# latch3.net
KiCad netlist of a schematic drawn in EAGLE
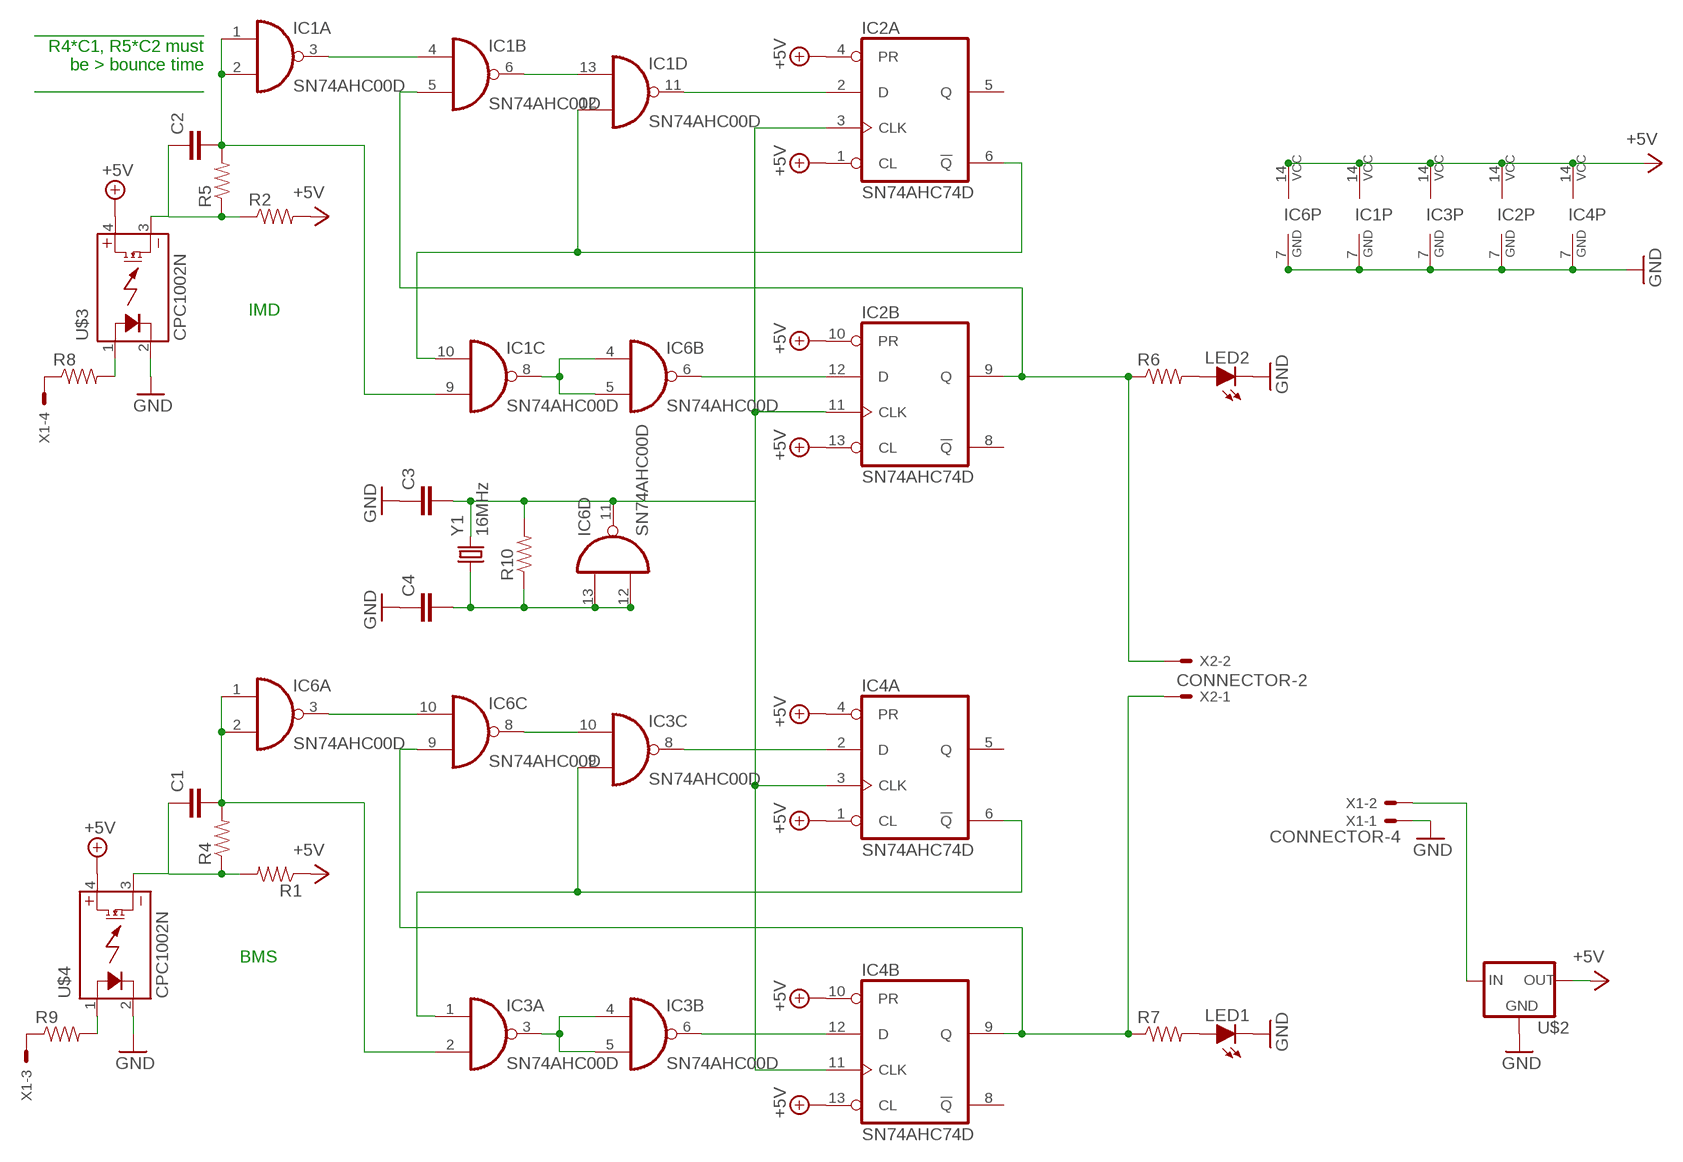
[diagram p0: schematic, sheet 1]

(export (version "E")
  (design (tool "Eeschema 10.0.6"))
  (components
    (comp (ref "C1")
      (value "CAP0402-CAP")
      (footprint "eagle-import:0402-CAP")
      (libsource (lib "eagle-import") (part "CAP0402-CAP"))
    )
    (comp (ref "C2")
      (value "CAP0402-CAP")
      (footprint "eagle-import:0402-CAP")
      (libsource (lib "eagle-import") (part "CAP0402-CAP"))
    )
    (comp (ref "C3")
      (value "CAP0402-CAP")
      (footprint "eagle-import:0402-CAP")
      (libsource (lib "eagle-import") (part "CAP0402-CAP"))
    )
    (comp (ref "C4")
      (value "CAP0402-CAP")
      (footprint "eagle-import:0402-CAP")
      (libsource (lib "eagle-import") (part "CAP0402-CAP"))
    )
    (comp (ref "IC1")
      (value "SN74AHC00D")
      (footprint "eagle-import:SOIC-14")
      (libsource (lib "eagle-import") (part "SN74AHC00D"))
    )
    (comp (ref "IC2")
      (value "SN74AHC74D")
      (footprint "eagle-import:SOIC-14")
      (libsource (lib "eagle-import") (part "SN74AHC74D"))
    )
    (comp (ref "IC3")
      (value "SN74AHC00D")
      (footprint "eagle-import:SOIC-14")
      (libsource (lib "eagle-import") (part "SN74AHC00D"))
    )
    (comp (ref "IC4")
      (value "SN74AHC74D")
      (footprint "eagle-import:SOIC-14")
      (libsource (lib "eagle-import") (part "SN74AHC74D"))
    )
    (comp (ref "IC6")
      (value "SN74AHC00D")
      (footprint "eagle-import:SOIC-14")
      (libsource (lib "eagle-import") (part "SN74AHC00D"))
    )
    (comp (ref "LED1")
      (value "LED-0805")
      (footprint "eagle-import:LED-805")
      (libsource (lib "eagle-import") (part "LED-0805"))
    )
    (comp (ref "LED2")
      (value "LED-0805")
      (footprint "eagle-import:LED-805")
      (libsource (lib "eagle-import") (part "LED-0805"))
    )
    (comp (ref "R1")
      (value "RESISTOR0402")
      (footprint "eagle-import:0402-RES")
      (libsource (lib "eagle-import") (part "RESISTOR0402"))
    )
    (comp (ref "R2")
      (value "RESISTOR0402")
      (footprint "eagle-import:0402-RES")
      (libsource (lib "eagle-import") (part "RESISTOR0402"))
    )
    (comp (ref "R4")
      (value "RESISTOR0402")
      (footprint "eagle-import:0402-RES")
      (libsource (lib "eagle-import") (part "RESISTOR0402"))
    )
    (comp (ref "R5")
      (value "RESISTOR0402")
      (footprint "eagle-import:0402-RES")
      (libsource (lib "eagle-import") (part "RESISTOR0402"))
    )
    (comp (ref "R6")
      (value "RESISTOR0402")
      (footprint "eagle-import:0402-RES")
      (libsource (lib "eagle-import") (part "RESISTOR0402"))
    )
    (comp (ref "R7")
      (value "RESISTOR0402")
      (footprint "eagle-import:0402-RES")
      (libsource (lib "eagle-import") (part "RESISTOR0402"))
    )
    (comp (ref "R8")
      (value "RESISTOR0402")
      (footprint "eagle-import:0402-RES")
      (libsource (lib "eagle-import") (part "RESISTOR0402"))
    )
    (comp (ref "R9")
      (value "RESISTOR0402")
      (footprint "eagle-import:0402-RES")
      (libsource (lib "eagle-import") (part "RESISTOR0402"))
    )
    (comp (ref "R10")
      (value "RESISTOR0402")
      (footprint "eagle-import:0402-RES")
      (libsource (lib "eagle-import") (part "RESISTOR0402"))
    )
    (comp (ref "U$2")
      (value "5VREG_LM340-NLM340MPX-5.0/NOPB")
      (footprint "eagle-import:SOT223")
      (libsource (lib "eagle-import") (part "5VREG_LM340-NLM340MPX-5.0/NOPB"))
    )
    (comp (ref "U$3")
      (value "CPC1002N")
      (footprint "eagle-import:SOP04")
      (libsource (lib "eagle-import") (part "CPC1002N"))
    )
    (comp (ref "U$4")
      (value "CPC1002N")
      (footprint "eagle-import:SOP04")
      (libsource (lib "eagle-import") (part "CPC1002N"))
    )
    (comp (ref "X1")
      (value "CONNECTOR-4")
      (footprint "eagle-import:MINIFIT_5566-4")
      (libsource (lib "eagle-import") (part "CONNECTOR-4"))
    )
    (comp (ref "X2")
      (value "CONNECTOR-2")
      (footprint "eagle-import:MINIFIT_5566-2")
      (libsource (lib "eagle-import") (part "CONNECTOR-2"))
    )
    (comp (ref "Y1")
      (value "16MHz")
      (footprint "eagle-import:CRYSTAL-SMD-3.2X1.5MM")
      (libsource (lib "eagle-import") (part "CRYSTAL3.2X1.5MM"))
    )
  )
  (nets
    (net (code "1") (name "+5V") (class "Default")
      (node (ref "IC1") (pin "14") (pinfunction "VCC_14") (pintype "power_in"))
      (node (ref "IC2") (pin "1") (pinfunction "CL_1") (pintype "input"))
      (node (ref "IC2") (pin "10") (pinfunction "PR_10") (pintype "input"))
      (node (ref "IC2") (pin "13") (pinfunction "CL_13") (pintype "input"))
      (node (ref "IC2") (pin "14") (pinfunction "VCC_14") (pintype "power_in"))
      (node (ref "IC2") (pin "4") (pinfunction "PR_4") (pintype "input"))
      (node (ref "IC3") (pin "14") (pinfunction "VCC_14") (pintype "power_in"))
      (node (ref "IC4") (pin "1") (pinfunction "CL_1") (pintype "input"))
      (node (ref "IC4") (pin "10") (pinfunction "PR_10") (pintype "input"))
      (node (ref "IC4") (pin "13") (pinfunction "CL_13") (pintype "input"))
      (node (ref "IC4") (pin "14") (pinfunction "VCC_14") (pintype "power_in"))
      (node (ref "IC4") (pin "4") (pinfunction "PR_4") (pintype "input"))
      (node (ref "IC6") (pin "14") (pinfunction "VCC_14") (pintype "power_in"))
      (node (ref "R1") (pin "1") (pinfunction "1_1") (pintype "passive"))
      (node (ref "R2") (pin "2") (pinfunction "2_2") (pintype "passive"))
      (node (ref "U$2") (pin "3") (pinfunction "OUT_3") (pintype "output"))
      (node (ref "U$3") (pin "4") (pinfunction "DC+_4") (pintype "passive"))
      (node (ref "U$4") (pin "4") (pinfunction "DC+_4") (pintype "passive"))
    )
    (net (code "2") (name "GND") (class "Default")
      (node (ref "C3") (pin "1") (pinfunction "1_1") (pintype "passive"))
      (node (ref "C4") (pin "1") (pinfunction "1_1") (pintype "passive"))
      (node (ref "IC1") (pin "7") (pinfunction "GND_7") (pintype "power_in"))
      (node (ref "IC2") (pin "7") (pinfunction "GND_7") (pintype "power_in"))
      (node (ref "IC3") (pin "7") (pinfunction "GND_7") (pintype "power_in"))
      (node (ref "IC4") (pin "7") (pinfunction "GND_7") (pintype "power_in"))
      (node (ref "IC6") (pin "7") (pinfunction "GND_7") (pintype "power_in"))
      (node (ref "LED1") (pin "C") (pinfunction "C_C") (pintype "passive"))
      (node (ref "LED2") (pin "C") (pinfunction "C_C") (pintype "passive"))
      (node (ref "U$2") (pin "2") (pinfunction "GND_2") (pintype "input"))
      (node (ref "U$2") (pin "4") (pinfunction "GND_4") (pintype "input"))
      (node (ref "U$3") (pin "2") (pinfunction "CONTROL-_2") (pintype "passive"))
      (node (ref "U$4") (pin "2") (pinfunction "CONTROL-_2") (pintype "passive"))
      (node (ref "X1") (pin "1") (pinfunction "S_1") (pintype "passive"))
    )
    (net (code "3") (name "Net-(IC1A-I0)") (class "Default")
      (node (ref "C2") (pin "2") (pinfunction "2_2") (pintype "passive"))
      (node (ref "IC1") (pin "1") (pinfunction "I0_1") (pintype "input"))
      (node (ref "IC1") (pin "2") (pinfunction "I1_2") (pintype "input"))
      (node (ref "IC1") (pin "9") (pinfunction "I1_9") (pintype "input"))
      (node (ref "R5") (pin "2") (pinfunction "2_2") (pintype "passive"))
    )
    (net (code "4") (name "Net-(IC1A-O)") (class "Default")
      (node (ref "IC1") (pin "3") (pinfunction "O_3") (pintype "output"))
      (node (ref "IC1") (pin "4") (pinfunction "I0_4") (pintype "input"))
    )
    (net (code "5") (name "Net-(IC1B-I1)") (class "Default")
      (node (ref "IC1") (pin "5") (pinfunction "I1_5") (pintype "input"))
      (node (ref "IC2") (pin "9") (pinfunction "Q_9") (pintype "output"))
      (node (ref "R6") (pin "1") (pinfunction "1_1") (pintype "passive"))
      (node (ref "X2") (pin "2") (pinfunction "S_2") (pintype "passive"))
    )
    (net (code "6") (name "Net-(IC1B-O)") (class "Default")
      (node (ref "IC1") (pin "13") (pinfunction "I0_13") (pintype "input"))
      (node (ref "IC1") (pin "6") (pinfunction "O_6") (pintype "output"))
    )
    (net (code "7") (name "Net-(IC1C-I0)") (class "Default")
      (node (ref "IC1") (pin "10") (pinfunction "I0_10") (pintype "input"))
      (node (ref "IC1") (pin "12") (pinfunction "I1_12") (pintype "input"))
      (node (ref "IC2") (pin "6") (pinfunction "~{Q}_6") (pintype "output"))
    )
    (net (code "8") (name "Net-(IC1C-O)") (class "Default")
      (node (ref "IC1") (pin "8") (pinfunction "O_8") (pintype "output"))
      (node (ref "IC6") (pin "4") (pinfunction "I0_4") (pintype "input"))
      (node (ref "IC6") (pin "5") (pinfunction "I1_5") (pintype "input"))
    )
    (net (code "9") (name "Net-(IC1D-O)") (class "Default")
      (node (ref "IC1") (pin "11") (pinfunction "O_11") (pintype "output"))
      (node (ref "IC2") (pin "2") (pinfunction "D_2") (pintype "input"))
    )
    (net (code "10") (name "Net-(IC2A-CLK)") (class "Default")
      (node (ref "C3") (pin "2") (pinfunction "2_2") (pintype "passive"))
      (node (ref "IC2") (pin "11") (pinfunction "CLK_11") (pintype "input"))
      (node (ref "IC2") (pin "3") (pinfunction "CLK_3") (pintype "input"))
      (node (ref "IC4") (pin "11") (pinfunction "CLK_11") (pintype "input"))
      (node (ref "IC4") (pin "3") (pinfunction "CLK_3") (pintype "input"))
      (node (ref "IC6") (pin "11") (pinfunction "O_11") (pintype "output"))
      (node (ref "R10") (pin "2") (pinfunction "2_2") (pintype "passive"))
      (node (ref "Y1") (pin "P$2") (pinfunction "2_P$2") (pintype "passive"))
    )
    (net (code "11") (name "Net-(IC2B-D)") (class "Default")
      (node (ref "IC2") (pin "12") (pinfunction "D_12") (pintype "input"))
      (node (ref "IC6") (pin "6") (pinfunction "O_6") (pintype "output"))
    )
    (net (code "12") (name "Net-(IC3A-I0)") (class "Default")
      (node (ref "IC3") (pin "1") (pinfunction "I0_1") (pintype "input"))
      (node (ref "IC3") (pin "9") (pinfunction "I1_9") (pintype "input"))
      (node (ref "IC4") (pin "6") (pinfunction "~{Q}_6") (pintype "output"))
    )
    (net (code "13") (name "Net-(IC3A-I1)") (class "Default")
      (node (ref "C1") (pin "2") (pinfunction "2_2") (pintype "passive"))
      (node (ref "IC3") (pin "2") (pinfunction "I1_2") (pintype "input"))
      (node (ref "IC6") (pin "1") (pinfunction "I0_1") (pintype "input"))
      (node (ref "IC6") (pin "2") (pinfunction "I1_2") (pintype "input"))
      (node (ref "R4") (pin "2") (pinfunction "2_2") (pintype "passive"))
    )
    (net (code "14") (name "Net-(IC3A-O)") (class "Default")
      (node (ref "IC3") (pin "3") (pinfunction "O_3") (pintype "output"))
      (node (ref "IC3") (pin "4") (pinfunction "I0_4") (pintype "input"))
      (node (ref "IC3") (pin "5") (pinfunction "I1_5") (pintype "input"))
    )
    (net (code "15") (name "Net-(IC3B-O)") (class "Default")
      (node (ref "IC3") (pin "6") (pinfunction "O_6") (pintype "output"))
      (node (ref "IC4") (pin "12") (pinfunction "D_12") (pintype "input"))
    )
    (net (code "16") (name "Net-(IC3C-I0)") (class "Default")
      (node (ref "IC3") (pin "10") (pinfunction "I0_10") (pintype "input"))
      (node (ref "IC6") (pin "8") (pinfunction "O_8") (pintype "output"))
    )
    (net (code "17") (name "Net-(IC3C-O)") (class "Default")
      (node (ref "IC3") (pin "8") (pinfunction "O_8") (pintype "output"))
      (node (ref "IC4") (pin "2") (pinfunction "D_2") (pintype "input"))
    )
    (net (code "18") (name "Net-(IC4B-Q)") (class "Default")
      (node (ref "IC4") (pin "9") (pinfunction "Q_9") (pintype "output"))
      (node (ref "IC6") (pin "9") (pinfunction "I1_9") (pintype "input"))
      (node (ref "R7") (pin "1") (pinfunction "1_1") (pintype "passive"))
      (node (ref "X2") (pin "1") (pinfunction "S_1") (pintype "passive"))
    )
    (net (code "19") (name "Net-(IC6A-O)") (class "Default")
      (node (ref "IC6") (pin "10") (pinfunction "I0_10") (pintype "input"))
      (node (ref "IC6") (pin "3") (pinfunction "O_3") (pintype "output"))
    )
    (net (code "20") (name "Net-(IC6D-I0)") (class "Default")
      (node (ref "C4") (pin "2") (pinfunction "2_2") (pintype "passive"))
      (node (ref "IC6") (pin "12") (pinfunction "I1_12") (pintype "input"))
      (node (ref "IC6") (pin "13") (pinfunction "I0_13") (pintype "input"))
      (node (ref "R10") (pin "1") (pinfunction "1_1") (pintype "passive"))
      (node (ref "Y1") (pin "P$1") (pinfunction "1_P$1") (pintype "passive"))
    )
    (net (code "21") (name "Net-(LED1-PadA)") (class "Default")
      (node (ref "LED1") (pin "A") (pinfunction "A_A") (pintype "passive"))
      (node (ref "R7") (pin "2") (pinfunction "2_2") (pintype "passive"))
    )
    (net (code "22") (name "Net-(LED2-PadA)") (class "Default")
      (node (ref "LED2") (pin "A") (pinfunction "A_A") (pintype "passive"))
      (node (ref "R6") (pin "2") (pinfunction "2_2") (pintype "passive"))
    )
    (net (code "23") (name "Net-(U$2-IN)") (class "Default")
      (node (ref "U$2") (pin "1") (pinfunction "IN_1") (pintype "input"))
      (node (ref "X1") (pin "2") (pinfunction "S_2") (pintype "passive"))
    )
    (net (code "24") (name "Net-(U$3-CONTROL+)") (class "Default")
      (node (ref "R8") (pin "2") (pinfunction "2_2") (pintype "passive"))
      (node (ref "U$3") (pin "1") (pinfunction "CONTROL+_1") (pintype "passive"))
    )
    (net (code "25") (name "Net-(U$3-DC-)") (class "Default")
      (node (ref "C2") (pin "1") (pinfunction "1_1") (pintype "passive"))
      (node (ref "R2") (pin "1") (pinfunction "1_1") (pintype "passive"))
      (node (ref "R5") (pin "1") (pinfunction "1_1") (pintype "passive"))
      (node (ref "U$3") (pin "3") (pinfunction "DC-_3") (pintype "passive"))
    )
    (net (code "26") (name "Net-(U$4-CONTROL+)") (class "Default")
      (node (ref "R9") (pin "2") (pinfunction "2_2") (pintype "passive"))
      (node (ref "U$4") (pin "1") (pinfunction "CONTROL+_1") (pintype "passive"))
    )
    (net (code "27") (name "Net-(U$4-DC-)") (class "Default")
      (node (ref "C1") (pin "1") (pinfunction "1_1") (pintype "passive"))
      (node (ref "R1") (pin "2") (pinfunction "2_2") (pintype "passive"))
      (node (ref "R4") (pin "1") (pinfunction "1_1") (pintype "passive"))
      (node (ref "U$4") (pin "3") (pinfunction "DC-_3") (pintype "passive"))
    )
    (net (code "28") (name "Net-(X1C-S)") (class "Default")
      (node (ref "R9") (pin "1") (pinfunction "1_1") (pintype "passive"))
      (node (ref "X1") (pin "3") (pinfunction "S_3") (pintype "passive"))
    )
    (net (code "29") (name "Net-(X1D-S)") (class "Default")
      (node (ref "R8") (pin "1") (pinfunction "1_1") (pintype "passive"))
      (node (ref "X1") (pin "4") (pinfunction "S_4") (pintype "passive"))
    )
    (net (code "30") (name "unconnected-(IC2A-Q-Pad5)") (class "Default")
      (node (ref "IC2") (pin "5") (pinfunction "Q_5") (pintype "output"))
    )
    (net (code "31") (name "unconnected-(IC2B-~{Q}-Pad8)") (class "Default")
      (node (ref "IC2") (pin "8") (pinfunction "~{Q}_8") (pintype "output"))
    )
    (net (code "32") (name "unconnected-(IC4A-Q-Pad5)") (class "Default")
      (node (ref "IC4") (pin "5") (pinfunction "Q_5") (pintype "output"))
    )
    (net (code "33") (name "unconnected-(IC4B-~{Q}-Pad8)") (class "Default")
      (node (ref "IC4") (pin "8") (pinfunction "~{Q}_8") (pintype "output"))
    )
  )
)
